# Driver.net
KiCad netlist of a schematic drawn in Altium Designer
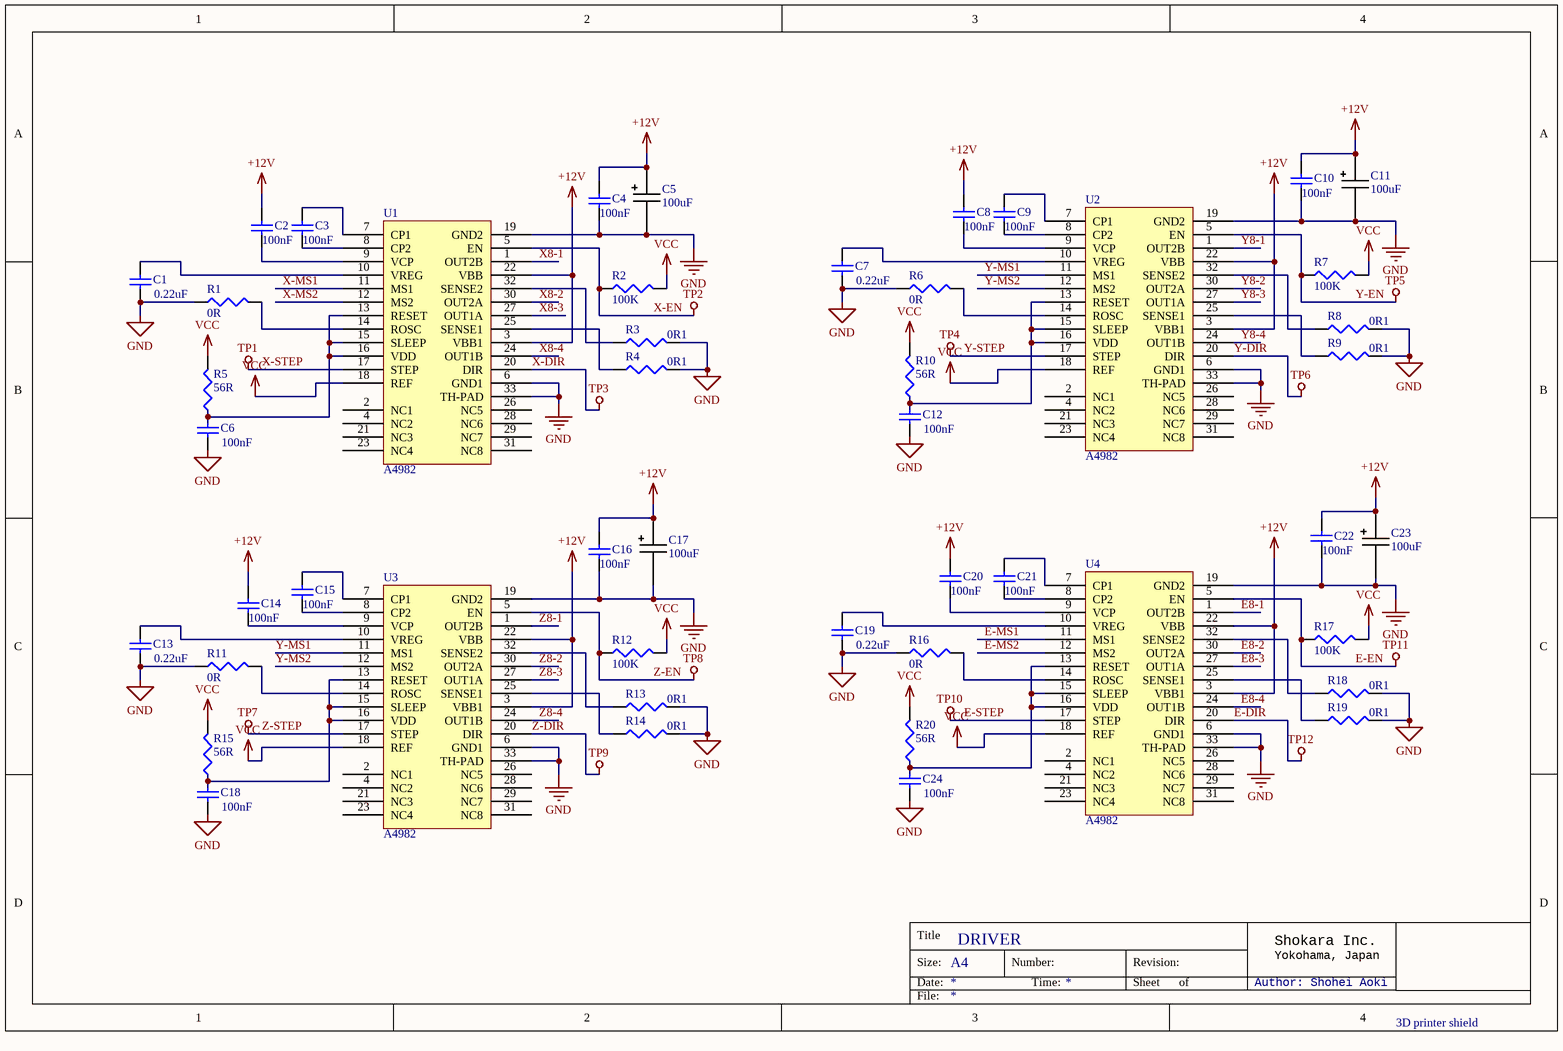
[diagram p0: Driver.SchDoc]

(export (version "E")
  (design (tool "Eeschema 10.0.6"))
  (components
    (comp (ref "C1")
      (value "0.22uF")
      (footprint "1608[0603]")
      (description "Capacitor (Semiconductor SIM Model)")
      (fields (field (name "PUBLISHER") "Altium Limited"))
      (libsource (lib "Miscellaneous Devices") (part "Cap Semi"))
    )
    (comp (ref "C2")
      (value "100nF")
      (footprint "1608[0603]")
      (description "Capacitor (Semiconductor SIM Model)")
      (fields (field (name "PUBLISHER") "Altium Limited"))
      (libsource (lib "Miscellaneous Devices") (part "Cap Semi"))
    )
    (comp (ref "C3")
      (value "100nF")
      (footprint "1608[0603]")
      (description "Capacitor (Semiconductor SIM Model)")
      (fields (field (name "PUBLISHER") "Altium Limited"))
      (libsource (lib "Miscellaneous Devices") (part "Cap Semi"))
    )
    (comp (ref "C4")
      (value "100nF")
      (footprint "1608[0603]")
      (description "Capacitor (Semiconductor SIM Model)")
      (fields (field (name "PUBLISHER") "Altium Limited"))
      (libsource (lib "Miscellaneous Devices") (part "Cap Semi"))
    )
    (comp (ref "C5")
      (value "*")
      (footprint "EEE-1HA470XP")
      (fields (field (name "ALTIUM_UNNAMED_1") "100uF"))
      (libsource (lib "3dprinter_shield") (part "Cap_alumi_electrolytic"))
    )
    (comp (ref "C6")
      (value "100nF")
      (footprint "1608[0603]")
      (description "Capacitor (Semiconductor SIM Model)")
      (fields (field (name "PUBLISHER") "Altium Limited"))
      (libsource (lib "Miscellaneous Devices") (part "Cap Semi"))
    )
    (comp (ref "C7")
      (value "0.22uF")
      (footprint "1608[0603]")
      (description "Capacitor (Semiconductor SIM Model)")
      (fields (field (name "PUBLISHER") "Altium Limited"))
      (libsource (lib "Miscellaneous Devices") (part "Cap Semi"))
    )
    (comp (ref "C8")
      (value "100nF")
      (footprint "1608[0603]")
      (description "Capacitor (Semiconductor SIM Model)")
      (fields (field (name "PUBLISHER") "Altium Limited"))
      (libsource (lib "Miscellaneous Devices") (part "Cap Semi"))
    )
    (comp (ref "C9")
      (value "100nF")
      (footprint "1608[0603]")
      (description "Capacitor (Semiconductor SIM Model)")
      (fields (field (name "PUBLISHER") "Altium Limited"))
      (libsource (lib "Miscellaneous Devices") (part "Cap Semi"))
    )
    (comp (ref "C10")
      (value "100nF")
      (footprint "1608[0603]")
      (description "Capacitor (Semiconductor SIM Model)")
      (fields (field (name "PUBLISHER") "Altium Limited"))
      (libsource (lib "Miscellaneous Devices") (part "Cap Semi"))
    )
    (comp (ref "C11")
      (value "*")
      (footprint "EEE-1HA470XP")
      (fields (field (name "ALTIUM_UNNAMED_1") "100uF"))
      (libsource (lib "3dprinter_shield") (part "Cap_alumi_electrolytic"))
    )
    (comp (ref "C12")
      (value "100nF")
      (footprint "1608[0603]")
      (description "Capacitor (Semiconductor SIM Model)")
      (fields (field (name "PUBLISHER") "Altium Limited"))
      (libsource (lib "Miscellaneous Devices") (part "Cap Semi"))
    )
    (comp (ref "C13")
      (value "0.22uF")
      (footprint "1608[0603]")
      (description "Capacitor (Semiconductor SIM Model)")
      (fields (field (name "PUBLISHER") "Altium Limited"))
      (libsource (lib "Miscellaneous Devices") (part "Cap Semi"))
    )
    (comp (ref "C14")
      (value "100nF")
      (footprint "1608[0603]")
      (description "Capacitor (Semiconductor SIM Model)")
      (fields (field (name "PUBLISHER") "Altium Limited"))
      (libsource (lib "Miscellaneous Devices") (part "Cap Semi"))
    )
    (comp (ref "C15")
      (value "100nF")
      (footprint "1608[0603]")
      (description "Capacitor (Semiconductor SIM Model)")
      (fields (field (name "PUBLISHER") "Altium Limited"))
      (libsource (lib "Miscellaneous Devices") (part "Cap Semi"))
    )
    (comp (ref "C16")
      (value "100nF")
      (footprint "1608[0603]")
      (description "Capacitor (Semiconductor SIM Model)")
      (fields (field (name "PUBLISHER") "Altium Limited"))
      (libsource (lib "Miscellaneous Devices") (part "Cap Semi"))
    )
    (comp (ref "C17")
      (value "*")
      (footprint "EEE-1HA470XP")
      (fields (field (name "ALTIUM_UNNAMED_1") "100uF"))
      (libsource (lib "3dprinter_shield") (part "Cap_alumi_electrolytic"))
    )
    (comp (ref "C18")
      (value "100nF")
      (footprint "1608[0603]")
      (description "Capacitor (Semiconductor SIM Model)")
      (fields (field (name "PUBLISHER") "Altium Limited"))
      (libsource (lib "Miscellaneous Devices") (part "Cap Semi"))
    )
    (comp (ref "C19")
      (value "0.22uF")
      (footprint "1608[0603]")
      (description "Capacitor (Semiconductor SIM Model)")
      (fields (field (name "PUBLISHER") "Altium Limited"))
      (libsource (lib "Miscellaneous Devices") (part "Cap Semi"))
    )
    (comp (ref "C20")
      (value "100nF")
      (footprint "1608[0603]")
      (description "Capacitor (Semiconductor SIM Model)")
      (fields (field (name "PUBLISHER") "Altium Limited"))
      (libsource (lib "Miscellaneous Devices") (part "Cap Semi"))
    )
    (comp (ref "C21")
      (value "100nF")
      (footprint "1608[0603]")
      (description "Capacitor (Semiconductor SIM Model)")
      (fields (field (name "PUBLISHER") "Altium Limited"))
      (libsource (lib "Miscellaneous Devices") (part "Cap Semi"))
    )
    (comp (ref "C22")
      (value "100nF")
      (footprint "1608[0603]")
      (description "Capacitor (Semiconductor SIM Model)")
      (fields (field (name "PUBLISHER") "Altium Limited"))
      (libsource (lib "Miscellaneous Devices") (part "Cap Semi"))
    )
    (comp (ref "C23")
      (value "*")
      (footprint "EEE-1HA470XP")
      (fields (field (name "ALTIUM_UNNAMED_1") "100uF"))
      (libsource (lib "3dprinter_shield") (part "Cap_alumi_electrolytic"))
    )
    (comp (ref "C24")
      (value "100nF")
      (footprint "1608[0603]")
      (description "Capacitor (Semiconductor SIM Model)")
      (fields (field (name "PUBLISHER") "Altium Limited"))
      (libsource (lib "Miscellaneous Devices") (part "Cap Semi"))
    )
    (comp (ref "R1")
      (value "0R")
      (footprint "J1-0603")
      (description "Resistor")
      (fields (field (name "PUBLISHER") "Altium Limited"))
      (libsource (lib "Miscellaneous Devices") (part "Res3"))
    )
    (comp (ref "R2")
      (value "100K")
      (footprint "J1-0603")
      (description "Resistor")
      (fields (field (name "PUBLISHER") "Altium Limited"))
      (libsource (lib "Miscellaneous Devices") (part "Res3"))
    )
    (comp (ref "R3")
      (value "0R1")
      (footprint "J1-0603")
      (description "Resistor")
      (fields (field (name "PUBLISHER") "Altium Limited"))
      (libsource (lib "Miscellaneous Devices") (part "Res3"))
    )
    (comp (ref "R4")
      (value "0R1")
      (footprint "J1-0603")
      (description "Resistor")
      (fields (field (name "PUBLISHER") "Altium Limited"))
      (libsource (lib "Miscellaneous Devices") (part "Res3"))
    )
    (comp (ref "R5")
      (value "56R")
      (footprint "J1-0603")
      (description "Resistor")
      (fields (field (name "PUBLISHER") "Altium Limited"))
      (libsource (lib "Miscellaneous Devices") (part "Res3"))
    )
    (comp (ref "R6")
      (value "0R")
      (footprint "J1-0603")
      (description "Resistor")
      (fields (field (name "PUBLISHER") "Altium Limited"))
      (libsource (lib "Miscellaneous Devices") (part "Res3"))
    )
    (comp (ref "R7")
      (value "100K")
      (footprint "J1-0603")
      (description "Resistor")
      (fields (field (name "PUBLISHER") "Altium Limited"))
      (libsource (lib "Miscellaneous Devices") (part "Res3"))
    )
    (comp (ref "R8")
      (value "0R1")
      (footprint "J1-0603")
      (description "Resistor")
      (fields (field (name "PUBLISHER") "Altium Limited"))
      (libsource (lib "Miscellaneous Devices") (part "Res3"))
    )
    (comp (ref "R9")
      (value "0R1")
      (footprint "J1-0603")
      (description "Resistor")
      (fields (field (name "PUBLISHER") "Altium Limited"))
      (libsource (lib "Miscellaneous Devices") (part "Res3"))
    )
    (comp (ref "R10")
      (value "56R")
      (footprint "J1-0603")
      (description "Resistor")
      (fields (field (name "PUBLISHER") "Altium Limited"))
      (libsource (lib "Miscellaneous Devices") (part "Res3"))
    )
    (comp (ref "R11")
      (value "0R")
      (footprint "J1-0603")
      (description "Resistor")
      (fields (field (name "PUBLISHER") "Altium Limited"))
      (libsource (lib "Miscellaneous Devices") (part "Res3"))
    )
    (comp (ref "R12")
      (value "100K")
      (footprint "J1-0603")
      (description "Resistor")
      (fields (field (name "PUBLISHER") "Altium Limited"))
      (libsource (lib "Miscellaneous Devices") (part "Res3"))
    )
    (comp (ref "R13")
      (value "0R1")
      (footprint "J1-0603")
      (description "Resistor")
      (fields (field (name "PUBLISHER") "Altium Limited"))
      (libsource (lib "Miscellaneous Devices") (part "Res3"))
    )
    (comp (ref "R14")
      (value "0R1")
      (footprint "J1-0603")
      (description "Resistor")
      (fields (field (name "PUBLISHER") "Altium Limited"))
      (libsource (lib "Miscellaneous Devices") (part "Res3"))
    )
    (comp (ref "R15")
      (value "56R")
      (footprint "J1-0603")
      (description "Resistor")
      (fields (field (name "PUBLISHER") "Altium Limited"))
      (libsource (lib "Miscellaneous Devices") (part "Res3"))
    )
    (comp (ref "R16")
      (value "0R")
      (footprint "J1-0603")
      (description "Resistor")
      (fields (field (name "PUBLISHER") "Altium Limited"))
      (libsource (lib "Miscellaneous Devices") (part "Res3"))
    )
    (comp (ref "R17")
      (value "100K")
      (footprint "J1-0603")
      (description "Resistor")
      (fields (field (name "PUBLISHER") "Altium Limited"))
      (libsource (lib "Miscellaneous Devices") (part "Res3"))
    )
    (comp (ref "R18")
      (value "0R1")
      (footprint "J1-0603")
      (description "Resistor")
      (fields (field (name "PUBLISHER") "Altium Limited"))
      (libsource (lib "Miscellaneous Devices") (part "Res3"))
    )
    (comp (ref "R19")
      (value "0R1")
      (footprint "J1-0603")
      (description "Resistor")
      (fields (field (name "PUBLISHER") "Altium Limited"))
      (libsource (lib "Miscellaneous Devices") (part "Res3"))
    )
    (comp (ref "R20")
      (value "56R")
      (footprint "J1-0603")
      (description "Resistor")
      (fields (field (name "PUBLISHER") "Altium Limited"))
      (libsource (lib "Miscellaneous Devices") (part "Res3"))
    )
    (comp (ref "U1")
      (value "A4982")
      (footprint "QFN50P500X500X100_HS-33N_2")
      (libsource (lib "3dprinter_shield") (part "A4982"))
    )
    (comp (ref "U2")
      (value "A4982")
      (footprint "QFN50P500X500X100_HS-33N_2")
      (libsource (lib "3dprinter_shield") (part "A4982"))
    )
    (comp (ref "U3")
      (value "A4982")
      (footprint "QFN50P500X500X100_HS-33N_2")
      (libsource (lib "3dprinter_shield") (part "A4982"))
    )
    (comp (ref "U4")
      (value "A4982")
      (footprint "QFN50P500X500X100_HS-33N_2")
      (libsource (lib "3dprinter_shield") (part "A4982"))
    )
  )
  (nets
    (net (code "1") (name "+12V") (class "Default")
      (node (ref "C10") (pin "2") (pinfunction "2_2") (pintype "passive"))
      (node (ref "C11") (pin "2") (pinfunction "2_2") (pintype "passive"))
      (node (ref "C14") (pin "2") (pinfunction "2_2") (pintype "passive"))
      (node (ref "C16") (pin "2") (pinfunction "2_2") (pintype "passive"))
      (node (ref "C17") (pin "2") (pinfunction "2_2") (pintype "passive"))
      (node (ref "C2") (pin "2") (pinfunction "2_2") (pintype "passive"))
      (node (ref "C20") (pin "2") (pinfunction "2_2") (pintype "passive"))
      (node (ref "C22") (pin "2") (pinfunction "2_2") (pintype "passive"))
      (node (ref "C23") (pin "2") (pinfunction "2_2") (pintype "passive"))
      (node (ref "C4") (pin "2") (pinfunction "2_2") (pintype "passive"))
      (node (ref "C5") (pin "2") (pinfunction "2_2") (pintype "passive"))
      (node (ref "C8") (pin "2") (pinfunction "2_2") (pintype "passive"))
      (node (ref "U1") (pin "22") (pinfunction "VBB_22") (pintype "passive"))
      (node (ref "U1") (pin "3") (pinfunction "VBB1_3") (pintype "passive"))
      (node (ref "U2") (pin "22") (pinfunction "VBB_22") (pintype "passive"))
      (node (ref "U2") (pin "3") (pinfunction "VBB1_3") (pintype "passive"))
      (node (ref "U3") (pin "22") (pinfunction "VBB_22") (pintype "passive"))
      (node (ref "U3") (pin "3") (pinfunction "VBB1_3") (pintype "passive"))
      (node (ref "U4") (pin "22") (pinfunction "VBB_22") (pintype "passive"))
      (node (ref "U4") (pin "3") (pinfunction "VBB1_3") (pintype "passive"))
    )
    (net (code "2") (name "/E-MS1") (class "Default")
      (node (ref "U4") (pin "11") (pinfunction "MS1_11") (pintype "passive"))
    )
    (net (code "3") (name "/E-MS2") (class "Default")
      (node (ref "U4") (pin "12") (pinfunction "MS2_12") (pintype "passive"))
    )
    (net (code "4") (name "/E8-1") (class "Default")
      (node (ref "U4") (pin "1") (pinfunction "OUT2B_1") (pintype "passive"))
    )
    (net (code "5") (name "/E8-2") (class "Default")
      (node (ref "U4") (pin "30") (pinfunction "OUT2A_30") (pintype "passive"))
    )
    (net (code "6") (name "/E8-3") (class "Default")
      (node (ref "U4") (pin "27") (pinfunction "OUT1A_27") (pintype "passive"))
    )
    (net (code "7") (name "/E8-4") (class "Default")
      (node (ref "U4") (pin "24") (pinfunction "OUT1B_24") (pintype "passive"))
    )
    (net (code "8") (name "/X-MS1") (class "Default")
      (node (ref "U1") (pin "11") (pinfunction "MS1_11") (pintype "passive"))
    )
    (net (code "9") (name "/X-MS2") (class "Default")
      (node (ref "U1") (pin "12") (pinfunction "MS2_12") (pintype "passive"))
    )
    (net (code "10") (name "/X8-1") (class "Default")
      (node (ref "U1") (pin "1") (pinfunction "OUT2B_1") (pintype "passive"))
    )
    (net (code "11") (name "/X8-2") (class "Default")
      (node (ref "U1") (pin "30") (pinfunction "OUT2A_30") (pintype "passive"))
    )
    (net (code "12") (name "/X8-3") (class "Default")
      (node (ref "U1") (pin "27") (pinfunction "OUT1A_27") (pintype "passive"))
    )
    (net (code "13") (name "/X8-4") (class "Default")
      (node (ref "U1") (pin "24") (pinfunction "OUT1B_24") (pintype "passive"))
    )
    (net (code "14") (name "/Y-MS1") (class "Default")
      (node (ref "U2") (pin "11") (pinfunction "MS1_11") (pintype "passive"))
      (node (ref "U3") (pin "11") (pinfunction "MS1_11") (pintype "passive"))
    )
    (net (code "15") (name "/Y-MS2") (class "Default")
      (node (ref "U2") (pin "12") (pinfunction "MS2_12") (pintype "passive"))
      (node (ref "U3") (pin "12") (pinfunction "MS2_12") (pintype "passive"))
    )
    (net (code "16") (name "/Y8-1") (class "Default")
      (node (ref "U2") (pin "1") (pinfunction "OUT2B_1") (pintype "passive"))
    )
    (net (code "17") (name "/Y8-2") (class "Default")
      (node (ref "U2") (pin "30") (pinfunction "OUT2A_30") (pintype "passive"))
    )
    (net (code "18") (name "/Y8-3") (class "Default")
      (node (ref "U2") (pin "27") (pinfunction "OUT1A_27") (pintype "passive"))
    )
    (net (code "19") (name "/Y8-4") (class "Default")
      (node (ref "U2") (pin "24") (pinfunction "OUT1B_24") (pintype "passive"))
    )
    (net (code "20") (name "/Z8-1") (class "Default")
      (node (ref "U3") (pin "1") (pinfunction "OUT2B_1") (pintype "passive"))
    )
    (net (code "21") (name "/Z8-2") (class "Default")
      (node (ref "U3") (pin "30") (pinfunction "OUT2A_30") (pintype "passive"))
    )
    (net (code "22") (name "/Z8-3") (class "Default")
      (node (ref "U3") (pin "27") (pinfunction "OUT1A_27") (pintype "passive"))
    )
    (net (code "23") (name "/Z8-4") (class "Default")
      (node (ref "U3") (pin "24") (pinfunction "OUT1B_24") (pintype "passive"))
    )
    (net (code "24") (name "GND") (class "Default")
      (node (ref "C1") (pin "1") (pinfunction "1_1") (pintype "passive"))
      (node (ref "C10") (pin "1") (pinfunction "1_1") (pintype "passive"))
      (node (ref "C11") (pin "1") (pinfunction "1_1") (pintype "passive"))
      (node (ref "C12") (pin "1") (pinfunction "1_1") (pintype "passive"))
      (node (ref "C13") (pin "1") (pinfunction "1_1") (pintype "passive"))
      (node (ref "C16") (pin "1") (pinfunction "1_1") (pintype "passive"))
      (node (ref "C17") (pin "1") (pinfunction "1_1") (pintype "passive"))
      (node (ref "C18") (pin "1") (pinfunction "1_1") (pintype "passive"))
      (node (ref "C19") (pin "1") (pinfunction "1_1") (pintype "passive"))
      (node (ref "C22") (pin "1") (pinfunction "1_1") (pintype "passive"))
      (node (ref "C23") (pin "1") (pinfunction "1_1") (pintype "passive"))
      (node (ref "C24") (pin "1") (pinfunction "1_1") (pintype "passive"))
      (node (ref "C4") (pin "1") (pinfunction "1_1") (pintype "passive"))
      (node (ref "C5") (pin "1") (pinfunction "1_1") (pintype "passive"))
      (node (ref "C6") (pin "1") (pinfunction "1_1") (pintype "passive"))
      (node (ref "C7") (pin "1") (pinfunction "1_1") (pintype "passive"))
      (node (ref "R1") (pin "1") (pinfunction "1_1") (pintype "passive"))
      (node (ref "R11") (pin "1") (pinfunction "1_1") (pintype "passive"))
      (node (ref "R13") (pin "2") (pinfunction "2_2") (pintype "passive"))
      (node (ref "R14") (pin "2") (pinfunction "2_2") (pintype "passive"))
      (node (ref "R16") (pin "1") (pinfunction "1_1") (pintype "passive"))
      (node (ref "R18") (pin "2") (pinfunction "2_2") (pintype "passive"))
      (node (ref "R19") (pin "2") (pinfunction "2_2") (pintype "passive"))
      (node (ref "R3") (pin "2") (pinfunction "2_2") (pintype "passive"))
      (node (ref "R4") (pin "2") (pinfunction "2_2") (pintype "passive"))
      (node (ref "R6") (pin "1") (pinfunction "1_1") (pintype "passive"))
      (node (ref "R8") (pin "2") (pinfunction "2_2") (pintype "passive"))
      (node (ref "R9") (pin "2") (pinfunction "2_2") (pintype "passive"))
      (node (ref "U1") (pin "19") (pinfunction "GND2_19") (pintype "passive"))
      (node (ref "U1") (pin "33") (pinfunction "TH-PAD_33") (pintype "passive"))
      (node (ref "U1") (pin "6") (pinfunction "GND1_6") (pintype "passive"))
      (node (ref "U2") (pin "19") (pinfunction "GND2_19") (pintype "passive"))
      (node (ref "U2") (pin "33") (pinfunction "TH-PAD_33") (pintype "passive"))
      (node (ref "U2") (pin "6") (pinfunction "GND1_6") (pintype "passive"))
      (node (ref "U3") (pin "19") (pinfunction "GND2_19") (pintype "passive"))
      (node (ref "U3") (pin "33") (pinfunction "TH-PAD_33") (pintype "passive"))
      (node (ref "U3") (pin "6") (pinfunction "GND1_6") (pintype "passive"))
      (node (ref "U4") (pin "19") (pinfunction "GND2_19") (pintype "passive"))
      (node (ref "U4") (pin "33") (pinfunction "TH-PAD_33") (pintype "passive"))
      (node (ref "U4") (pin "6") (pinfunction "GND1_6") (pintype "passive"))
    )
    (net (code "25") (name "Net-(U1-CP1)") (class "Default")
      (node (ref "C3") (pin "2") (pinfunction "2_2") (pintype "passive"))
      (node (ref "U1") (pin "7") (pinfunction "CP1_7") (pintype "passive"))
    )
    (net (code "26") (name "Net-(U1-CP2)") (class "Default")
      (node (ref "C3") (pin "1") (pinfunction "1_1") (pintype "passive"))
      (node (ref "U1") (pin "8") (pinfunction "CP2_8") (pintype "passive"))
    )
    (net (code "27") (name "Net-(U1-RESET)") (class "Default")
      (node (ref "C6") (pin "2") (pinfunction "2_2") (pintype "passive"))
      (node (ref "R5") (pin "1") (pinfunction "1_1") (pintype "passive"))
      (node (ref "U1") (pin "13") (pinfunction "RESET_13") (pintype "passive"))
      (node (ref "U1") (pin "15") (pinfunction "SLEEP_15") (pintype "passive"))
      (node (ref "U1") (pin "16") (pinfunction "VDD_16") (pintype "passive"))
    )
    (net (code "28") (name "Net-(U1-ROSC)") (class "Default")
      (node (ref "R1") (pin "2") (pinfunction "2_2") (pintype "passive"))
      (node (ref "U1") (pin "14") (pinfunction "ROSC_14") (pintype "passive"))
    )
    (net (code "29") (name "Net-(U1-SENSE1)") (class "Default")
      (node (ref "R4") (pin "1") (pinfunction "1_1") (pintype "passive"))
      (node (ref "U1") (pin "25") (pinfunction "SENSE1_25") (pintype "passive"))
    )
    (net (code "30") (name "Net-(U1-SENSE2)") (class "Default")
      (node (ref "R3") (pin "1") (pinfunction "1_1") (pintype "passive"))
      (node (ref "U1") (pin "32") (pinfunction "SENSE2_32") (pintype "passive"))
    )
    (net (code "31") (name "Net-(U1-VCP)") (class "Default")
      (node (ref "C2") (pin "1") (pinfunction "1_1") (pintype "passive"))
      (node (ref "U1") (pin "9") (pinfunction "VCP_9") (pintype "passive"))
    )
    (net (code "32") (name "Net-(U1-VREG)") (class "Default")
      (node (ref "C1") (pin "2") (pinfunction "2_2") (pintype "passive"))
      (node (ref "U1") (pin "10") (pinfunction "VREG_10") (pintype "passive"))
    )
    (net (code "33") (name "Net-(U2-CP1)") (class "Default")
      (node (ref "C9") (pin "2") (pinfunction "2_2") (pintype "passive"))
      (node (ref "U2") (pin "7") (pinfunction "CP1_7") (pintype "passive"))
    )
    (net (code "34") (name "Net-(U2-CP2)") (class "Default")
      (node (ref "C9") (pin "1") (pinfunction "1_1") (pintype "passive"))
      (node (ref "U2") (pin "8") (pinfunction "CP2_8") (pintype "passive"))
    )
    (net (code "35") (name "Net-(U2-RESET)") (class "Default")
      (node (ref "C12") (pin "2") (pinfunction "2_2") (pintype "passive"))
      (node (ref "R10") (pin "1") (pinfunction "1_1") (pintype "passive"))
      (node (ref "U2") (pin "13") (pinfunction "RESET_13") (pintype "passive"))
      (node (ref "U2") (pin "15") (pinfunction "SLEEP_15") (pintype "passive"))
      (node (ref "U2") (pin "16") (pinfunction "VDD_16") (pintype "passive"))
    )
    (net (code "36") (name "Net-(U2-ROSC)") (class "Default")
      (node (ref "R6") (pin "2") (pinfunction "2_2") (pintype "passive"))
      (node (ref "U2") (pin "14") (pinfunction "ROSC_14") (pintype "passive"))
    )
    (net (code "37") (name "Net-(U2-SENSE1)") (class "Default")
      (node (ref "R9") (pin "1") (pinfunction "1_1") (pintype "passive"))
      (node (ref "U2") (pin "25") (pinfunction "SENSE1_25") (pintype "passive"))
    )
    (net (code "38") (name "Net-(U2-SENSE2)") (class "Default")
      (node (ref "R8") (pin "1") (pinfunction "1_1") (pintype "passive"))
      (node (ref "U2") (pin "32") (pinfunction "SENSE2_32") (pintype "passive"))
    )
    (net (code "39") (name "Net-(U2-VCP)") (class "Default")
      (node (ref "C8") (pin "1") (pinfunction "1_1") (pintype "passive"))
      (node (ref "U2") (pin "9") (pinfunction "VCP_9") (pintype "passive"))
    )
    (net (code "40") (name "Net-(U2-VREG)") (class "Default")
      (node (ref "C7") (pin "2") (pinfunction "2_2") (pintype "passive"))
      (node (ref "U2") (pin "10") (pinfunction "VREG_10") (pintype "passive"))
    )
    (net (code "41") (name "Net-(U3-CP1)") (class "Default")
      (node (ref "C15") (pin "2") (pinfunction "2_2") (pintype "passive"))
      (node (ref "U3") (pin "7") (pinfunction "CP1_7") (pintype "passive"))
    )
    (net (code "42") (name "Net-(U3-CP2)") (class "Default")
      (node (ref "C15") (pin "1") (pinfunction "1_1") (pintype "passive"))
      (node (ref "U3") (pin "8") (pinfunction "CP2_8") (pintype "passive"))
    )
    (net (code "43") (name "Net-(U3-RESET)") (class "Default")
      (node (ref "C18") (pin "2") (pinfunction "2_2") (pintype "passive"))
      (node (ref "R15") (pin "1") (pinfunction "1_1") (pintype "passive"))
      (node (ref "U3") (pin "13") (pinfunction "RESET_13") (pintype "passive"))
      (node (ref "U3") (pin "15") (pinfunction "SLEEP_15") (pintype "passive"))
      (node (ref "U3") (pin "16") (pinfunction "VDD_16") (pintype "passive"))
    )
    (net (code "44") (name "Net-(U3-ROSC)") (class "Default")
      (node (ref "R11") (pin "2") (pinfunction "2_2") (pintype "passive"))
      (node (ref "U3") (pin "14") (pinfunction "ROSC_14") (pintype "passive"))
    )
    (net (code "45") (name "Net-(U3-SENSE1)") (class "Default")
      (node (ref "R14") (pin "1") (pinfunction "1_1") (pintype "passive"))
      (node (ref "U3") (pin "25") (pinfunction "SENSE1_25") (pintype "passive"))
    )
    (net (code "46") (name "Net-(U3-SENSE2)") (class "Default")
      (node (ref "R13") (pin "1") (pinfunction "1_1") (pintype "passive"))
      (node (ref "U3") (pin "32") (pinfunction "SENSE2_32") (pintype "passive"))
    )
    (net (code "47") (name "Net-(U3-VCP)") (class "Default")
      (node (ref "C14") (pin "1") (pinfunction "1_1") (pintype "passive"))
      (node (ref "U3") (pin "9") (pinfunction "VCP_9") (pintype "passive"))
    )
    (net (code "48") (name "Net-(U3-VREG)") (class "Default")
      (node (ref "C13") (pin "2") (pinfunction "2_2") (pintype "passive"))
      (node (ref "U3") (pin "10") (pinfunction "VREG_10") (pintype "passive"))
    )
    (net (code "49") (name "Net-(U4-CP1)") (class "Default")
      (node (ref "C21") (pin "2") (pinfunction "2_2") (pintype "passive"))
      (node (ref "U4") (pin "7") (pinfunction "CP1_7") (pintype "passive"))
    )
    (net (code "50") (name "Net-(U4-CP2)") (class "Default")
      (node (ref "C21") (pin "1") (pinfunction "1_1") (pintype "passive"))
      (node (ref "U4") (pin "8") (pinfunction "CP2_8") (pintype "passive"))
    )
    (net (code "51") (name "Net-(U4-RESET)") (class "Default")
      (node (ref "C24") (pin "2") (pinfunction "2_2") (pintype "passive"))
      (node (ref "R20") (pin "1") (pinfunction "1_1") (pintype "passive"))
      (node (ref "U4") (pin "13") (pinfunction "RESET_13") (pintype "passive"))
      (node (ref "U4") (pin "15") (pinfunction "SLEEP_15") (pintype "passive"))
      (node (ref "U4") (pin "16") (pinfunction "VDD_16") (pintype "passive"))
    )
    (net (code "52") (name "Net-(U4-ROSC)") (class "Default")
      (node (ref "R16") (pin "2") (pinfunction "2_2") (pintype "passive"))
      (node (ref "U4") (pin "14") (pinfunction "ROSC_14") (pintype "passive"))
    )
    (net (code "53") (name "Net-(U4-SENSE1)") (class "Default")
      (node (ref "R19") (pin "1") (pinfunction "1_1") (pintype "passive"))
      (node (ref "U4") (pin "25") (pinfunction "SENSE1_25") (pintype "passive"))
    )
    (net (code "54") (name "Net-(U4-SENSE2)") (class "Default")
      (node (ref "R18") (pin "1") (pinfunction "1_1") (pintype "passive"))
      (node (ref "U4") (pin "32") (pinfunction "SENSE2_32") (pintype "passive"))
    )
    (net (code "55") (name "Net-(U4-VCP)") (class "Default")
      (node (ref "C20") (pin "1") (pinfunction "1_1") (pintype "passive"))
      (node (ref "U4") (pin "9") (pinfunction "VCP_9") (pintype "passive"))
    )
    (net (code "56") (name "Net-(U4-VREG)") (class "Default")
      (node (ref "C19") (pin "2") (pinfunction "2_2") (pintype "passive"))
      (node (ref "U4") (pin "10") (pinfunction "VREG_10") (pintype "passive"))
    )
    (net (code "57") (name "TP1") (class "Default")
      (node (ref "U1") (pin "17") (pinfunction "STEP_17") (pintype "passive"))
    )
    (net (code "58") (name "TP2") (class "Default")
      (node (ref "R2") (pin "1") (pinfunction "1_1") (pintype "passive"))
      (node (ref "U1") (pin "5") (pinfunction "EN_5") (pintype "passive"))
    )
    (net (code "59") (name "TP3") (class "Default")
      (node (ref "U1") (pin "20") (pinfunction "DIR_20") (pintype "passive"))
    )
    (net (code "60") (name "TP4") (class "Default")
      (node (ref "U2") (pin "17") (pinfunction "STEP_17") (pintype "passive"))
    )
    (net (code "61") (name "TP5") (class "Default")
      (node (ref "R7") (pin "1") (pinfunction "1_1") (pintype "passive"))
      (node (ref "U2") (pin "5") (pinfunction "EN_5") (pintype "passive"))
    )
    (net (code "62") (name "TP6") (class "Default")
      (node (ref "U2") (pin "20") (pinfunction "DIR_20") (pintype "passive"))
    )
    (net (code "63") (name "TP7") (class "Default")
      (node (ref "U3") (pin "17") (pinfunction "STEP_17") (pintype "passive"))
    )
    (net (code "64") (name "TP8") (class "Default")
      (node (ref "R12") (pin "1") (pinfunction "1_1") (pintype "passive"))
      (node (ref "U3") (pin "5") (pinfunction "EN_5") (pintype "passive"))
    )
    (net (code "65") (name "TP9") (class "Default")
      (node (ref "U3") (pin "20") (pinfunction "DIR_20") (pintype "passive"))
    )
    (net (code "66") (name "TP10") (class "Default")
      (node (ref "U4") (pin "17") (pinfunction "STEP_17") (pintype "passive"))
    )
    (net (code "67") (name "TP11") (class "Default")
      (node (ref "R17") (pin "1") (pinfunction "1_1") (pintype "passive"))
      (node (ref "U4") (pin "5") (pinfunction "EN_5") (pintype "passive"))
    )
    (net (code "68") (name "TP12") (class "Default")
      (node (ref "U4") (pin "20") (pinfunction "DIR_20") (pintype "passive"))
    )
    (net (code "69") (name "VCC") (class "Default")
      (node (ref "R10") (pin "2") (pinfunction "2_2") (pintype "passive"))
      (node (ref "R12") (pin "2") (pinfunction "2_2") (pintype "passive"))
      (node (ref "R15") (pin "2") (pinfunction "2_2") (pintype "passive"))
      (node (ref "R17") (pin "2") (pinfunction "2_2") (pintype "passive"))
      (node (ref "R2") (pin "2") (pinfunction "2_2") (pintype "passive"))
      (node (ref "R20") (pin "2") (pinfunction "2_2") (pintype "passive"))
      (node (ref "R5") (pin "2") (pinfunction "2_2") (pintype "passive"))
      (node (ref "R7") (pin "2") (pinfunction "2_2") (pintype "passive"))
      (node (ref "U1") (pin "18") (pinfunction "REF_18") (pintype "passive"))
      (node (ref "U2") (pin "18") (pinfunction "REF_18") (pintype "passive"))
      (node (ref "U3") (pin "18") (pinfunction "REF_18") (pintype "passive"))
      (node (ref "U4") (pin "18") (pinfunction "REF_18") (pintype "passive"))
    )
    (net (code "70") (name "unconnected-(U1-NC1-Pad2)") (class "Default")
      (node (ref "U1") (pin "2") (pinfunction "NC1_2") (pintype "passive"))
    )
    (net (code "71") (name "unconnected-(U1-NC2-Pad4)") (class "Default")
      (node (ref "U1") (pin "4") (pinfunction "NC2_4") (pintype "passive"))
    )
    (net (code "72") (name "unconnected-(U1-NC3-Pad21)") (class "Default")
      (node (ref "U1") (pin "21") (pinfunction "NC3_21") (pintype "passive"))
    )
    (net (code "73") (name "unconnected-(U1-NC4-Pad23)") (class "Default")
      (node (ref "U1") (pin "23") (pinfunction "NC4_23") (pintype "passive"))
    )
    (net (code "74") (name "unconnected-(U1-NC5-Pad26)") (class "Default")
      (node (ref "U1") (pin "26") (pinfunction "NC5_26") (pintype "passive"))
    )
    (net (code "75") (name "unconnected-(U1-NC6-Pad28)") (class "Default")
      (node (ref "U1") (pin "28") (pinfunction "NC6_28") (pintype "passive"))
    )
    (net (code "76") (name "unconnected-(U1-NC7-Pad29)") (class "Default")
      (node (ref "U1") (pin "29") (pinfunction "NC7_29") (pintype "passive"))
    )
    (net (code "77") (name "unconnected-(U1-NC8-Pad31)") (class "Default")
      (node (ref "U1") (pin "31") (pinfunction "NC8_31") (pintype "passive"))
    )
    (net (code "78") (name "unconnected-(U2-NC1-Pad2)") (class "Default")
      (node (ref "U2") (pin "2") (pinfunction "NC1_2") (pintype "passive"))
    )
    (net (code "79") (name "unconnected-(U2-NC2-Pad4)") (class "Default")
      (node (ref "U2") (pin "4") (pinfunction "NC2_4") (pintype "passive"))
    )
    (net (code "80") (name "unconnected-(U2-NC3-Pad21)") (class "Default")
      (node (ref "U2") (pin "21") (pinfunction "NC3_21") (pintype "passive"))
    )
    (net (code "81") (name "unconnected-(U2-NC4-Pad23)") (class "Default")
      (node (ref "U2") (pin "23") (pinfunction "NC4_23") (pintype "passive"))
    )
    (net (code "82") (name "unconnected-(U2-NC5-Pad26)") (class "Default")
      (node (ref "U2") (pin "26") (pinfunction "NC5_26") (pintype "passive"))
    )
    (net (code "83") (name "unconnected-(U2-NC6-Pad28)") (class "Default")
      (node (ref "U2") (pin "28") (pinfunction "NC6_28") (pintype "passive"))
    )
    (net (code "84") (name "unconnected-(U2-NC7-Pad29)") (class "Default")
      (node (ref "U2") (pin "29") (pinfunction "NC7_29") (pintype "passive"))
    )
    (net (code "85") (name "unconnected-(U2-NC8-Pad31)") (class "Default")
      (node (ref "U2") (pin "31") (pinfunction "NC8_31") (pintype "passive"))
    )
    (net (code "86") (name "unconnected-(U3-NC1-Pad2)") (class "Default")
      (node (ref "U3") (pin "2") (pinfunction "NC1_2") (pintype "passive"))
    )
    (net (code "87") (name "unconnected-(U3-NC2-Pad4)") (class "Default")
      (node (ref "U3") (pin "4") (pinfunction "NC2_4") (pintype "passive"))
    )
    (net (code "88") (name "unconnected-(U3-NC3-Pad21)") (class "Default")
      (node (ref "U3") (pin "21") (pinfunction "NC3_21") (pintype "passive"))
    )
    (net (code "89") (name "unconnected-(U3-NC4-Pad23)") (class "Default")
      (node (ref "U3") (pin "23") (pinfunction "NC4_23") (pintype "passive"))
    )
    (net (code "90") (name "unconnected-(U3-NC5-Pad26)") (class "Default")
      (node (ref "U3") (pin "26") (pinfunction "NC5_26") (pintype "passive"))
    )
    (net (code "91") (name "unconnected-(U3-NC6-Pad28)") (class "Default")
      (node (ref "U3") (pin "28") (pinfunction "NC6_28") (pintype "passive"))
    )
    (net (code "92") (name "unconnected-(U3-NC7-Pad29)") (class "Default")
      (node (ref "U3") (pin "29") (pinfunction "NC7_29") (pintype "passive"))
    )
    (net (code "93") (name "unconnected-(U3-NC8-Pad31)") (class "Default")
      (node (ref "U3") (pin "31") (pinfunction "NC8_31") (pintype "passive"))
    )
    (net (code "94") (name "unconnected-(U4-NC1-Pad2)") (class "Default")
      (node (ref "U4") (pin "2") (pinfunction "NC1_2") (pintype "passive"))
    )
    (net (code "95") (name "unconnected-(U4-NC2-Pad4)") (class "Default")
      (node (ref "U4") (pin "4") (pinfunction "NC2_4") (pintype "passive"))
    )
    (net (code "96") (name "unconnected-(U4-NC3-Pad21)") (class "Default")
      (node (ref "U4") (pin "21") (pinfunction "NC3_21") (pintype "passive"))
    )
    (net (code "97") (name "unconnected-(U4-NC4-Pad23)") (class "Default")
      (node (ref "U4") (pin "23") (pinfunction "NC4_23") (pintype "passive"))
    )
    (net (code "98") (name "unconnected-(U4-NC5-Pad26)") (class "Default")
      (node (ref "U4") (pin "26") (pinfunction "NC5_26") (pintype "passive"))
    )
    (net (code "99") (name "unconnected-(U4-NC6-Pad28)") (class "Default")
      (node (ref "U4") (pin "28") (pinfunction "NC6_28") (pintype "passive"))
    )
    (net (code "100") (name "unconnected-(U4-NC7-Pad29)") (class "Default")
      (node (ref "U4") (pin "29") (pinfunction "NC7_29") (pintype "passive"))
    )
    (net (code "101") (name "unconnected-(U4-NC8-Pad31)") (class "Default")
      (node (ref "U4") (pin "31") (pinfunction "NC8_31") (pintype "passive"))
    )
  )
)
